# MCU.net
KiCad netlist of a schematic drawn in Altium Designer
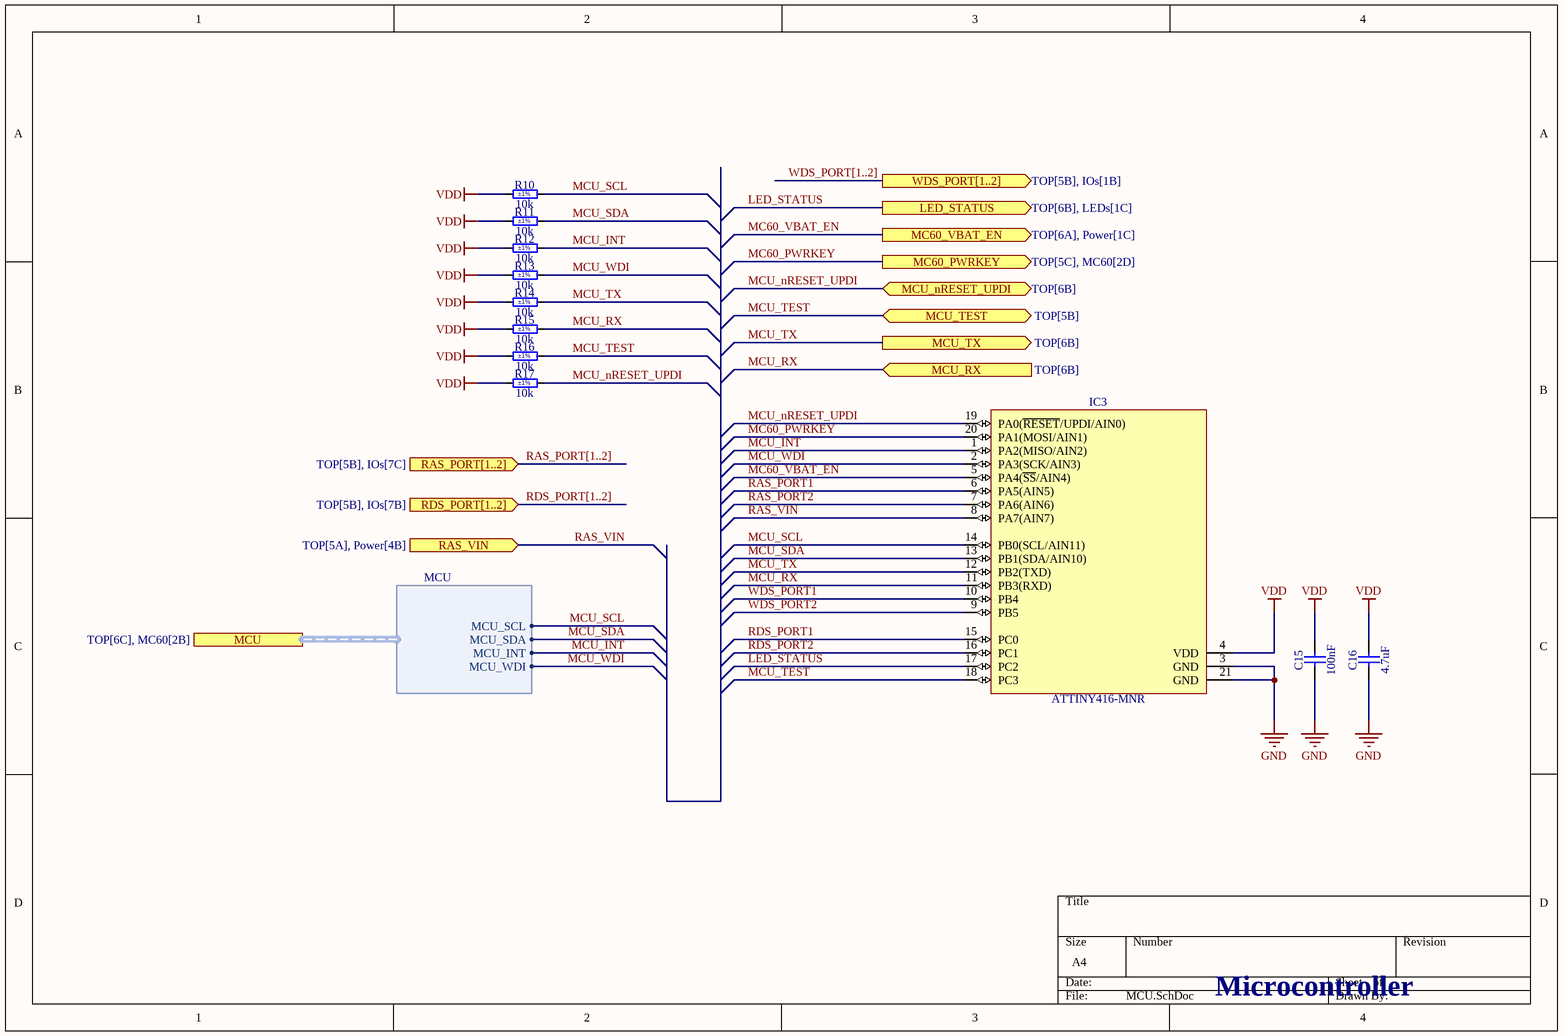
[diagram p0: MCU.SchDoc]

(export (version "E")
  (design (tool "Eeschema 10.0.6"))
  (components
    (comp (ref "C15")
      (value "100nF")
      (footprint "CAPC1608X87N")
      (description "Non-polarised capacitor")
      (fields
        (field (name "PART NUMBER") "CC0603_100NF_50V_10%_X7R")
        (field (name "VOLTAGE") "50V")
        (field (name "AUTHOR") "CERN DEM JLC")
      )
      (libsource (lib "Capacitors") (part "Capacitor - non polarized"))
    )
    (comp (ref "C16")
      (value "4.7uF")
      (footprint "CAPC1709X95N")
      (description "Non-polarised capacitor")
      (fields
        (field (name "PART NUMBER") "CC0603_4.7UF_16V_10%_X5R")
        (field (name "VOLTAGE") "16V")
        (field (name "AUTHOR") "CERN DEM JLC")
      )
      (libsource (lib "Capacitors") (part "Capacitor - non polarized"))
    )
    (comp (ref "IC3")
      (value "ATTINY416-MNR")
      (footprint "QFN40P300X300X80-21N-S180")
      (fields (field (name "MANUFACTURER") "MICROCHIP TECHNOLOGY") (field (name "AUTHOR") "Xusniyor"))
      (libsource (lib "ICs And Semiconductors") (part "ATTINY416-MNR"))
    )
    (comp (ref "R10")
      (value "10k")
      (footprint "RESC1608X55N")
      (description "Resistor - 1%")
      (fields
        (field (name "TOLERANCE") "±1%")
        (field (name "PART NUMBER") "R0603_10K_1%_0.1W_100PPM")
        (field (name "POWER") "0.1W")
        (field (name "AUTHOR") "CERN DEM JLC")
      )
      (libsource (lib "Resistors") (part "Resistor - 1%"))
    )
    (comp (ref "R11")
      (value "10k")
      (footprint "RESC1608X55N")
      (description "Resistor - 1%")
      (fields
        (field (name "TOLERANCE") "±1%")
        (field (name "PART NUMBER") "R0603_10K_1%_0.1W_100PPM")
        (field (name "POWER") "0.1W")
        (field (name "AUTHOR") "CERN DEM JLC")
      )
      (libsource (lib "Resistors") (part "Resistor - 1%"))
    )
    (comp (ref "R12")
      (value "10k")
      (footprint "RESC1608X55N")
      (description "Resistor - 1%")
      (fields
        (field (name "TOLERANCE") "±1%")
        (field (name "PART NUMBER") "R0603_10K_1%_0.1W_100PPM")
        (field (name "POWER") "0.1W")
        (field (name "AUTHOR") "CERN DEM JLC")
      )
      (libsource (lib "Resistors") (part "Resistor - 1%"))
    )
    (comp (ref "R13")
      (value "10k")
      (footprint "RESC1608X55N")
      (description "Resistor - 1%")
      (fields
        (field (name "TOLERANCE") "±1%")
        (field (name "PART NUMBER") "R0603_10K_1%_0.1W_100PPM")
        (field (name "POWER") "0.1W")
        (field (name "AUTHOR") "CERN DEM JLC")
      )
      (libsource (lib "Resistors") (part "Resistor - 1%"))
    )
    (comp (ref "R14")
      (value "10k")
      (footprint "RESC1608X55N")
      (description "Resistor - 1%")
      (fields
        (field (name "TOLERANCE") "±1%")
        (field (name "PART NUMBER") "R0603_10K_1%_0.1W_100PPM")
        (field (name "POWER") "0.1W")
        (field (name "AUTHOR") "CERN DEM JLC")
      )
      (libsource (lib "Resistors") (part "Resistor - 1%"))
    )
    (comp (ref "R15")
      (value "10k")
      (footprint "RESC1608X55N")
      (description "Resistor - 1%")
      (fields
        (field (name "TOLERANCE") "±1%")
        (field (name "PART NUMBER") "R0603_10K_1%_0.1W_100PPM")
        (field (name "POWER") "0.1W")
        (field (name "AUTHOR") "CERN DEM JLC")
      )
      (libsource (lib "Resistors") (part "Resistor - 1%"))
    )
    (comp (ref "R16")
      (value "10k")
      (footprint "RESC1608X55N")
      (description "Resistor - 1%")
      (fields
        (field (name "TOLERANCE") "±1%")
        (field (name "PART NUMBER") "R0603_10K_1%_0.1W_100PPM")
        (field (name "POWER") "0.1W")
        (field (name "AUTHOR") "CERN DEM JLC")
      )
      (libsource (lib "Resistors") (part "Resistor - 1%"))
    )
    (comp (ref "R17")
      (value "10k")
      (footprint "RESC1608X55N")
      (description "Resistor - 1%")
      (fields
        (field (name "TOLERANCE") "±1%")
        (field (name "PART NUMBER") "R0603_10K_1%_0.1W_100PPM")
        (field (name "POWER") "0.1W")
        (field (name "AUTHOR") "CERN DEM JLC")
      )
      (libsource (lib "Resistors") (part "Resistor - 1%"))
    )
  )
  (nets
    (net (code "2") (name "/LED_STATUS") (class "Default")
      (node (ref "IC3") (pin "17") (pinfunction "PC2_17") (pintype "bidirectional"))
    )
    (net (code "3") (name "/MC60_PWRKEY") (class "Default")
      (node (ref "IC3") (pin "20") (pinfunction "PA1(MOSI/AIN1)_20") (pintype "bidirectional"))
    )
    (net (code "4") (name "/MC60_VBAT_EN") (class "Default")
      (node (ref "IC3") (pin "5") (pinfunction "PA4(~{SS}/AIN4)_5") (pintype "bidirectional"))
    )
    (net (code "5") (name "/MCU_INT") (class "Default")
      (node (ref "IC3") (pin "1") (pinfunction "PA2(MISO/AIN2)_1") (pintype "bidirectional"))
      (node (ref "R12") (pin "2") (pinfunction "2_2") (pintype "passive"))
    )
    (net (code "6") (name "/MCU_RX") (class "Default")
      (node (ref "IC3") (pin "11") (pinfunction "PB3(RXD)_11") (pintype "bidirectional"))
      (node (ref "R15") (pin "2") (pinfunction "2_2") (pintype "passive"))
    )
    (net (code "7") (name "/MCU_SCL") (class "Default")
      (node (ref "IC3") (pin "14") (pinfunction "PB0(SCL/AIN11)_14") (pintype "bidirectional"))
      (node (ref "R10") (pin "2") (pinfunction "2_2") (pintype "passive"))
    )
    (net (code "8") (name "/MCU_SDA") (class "Default")
      (node (ref "IC3") (pin "13") (pinfunction "PB1(SDA/AIN10)_13") (pintype "bidirectional"))
      (node (ref "R11") (pin "2") (pinfunction "2_2") (pintype "passive"))
    )
    (net (code "9") (name "/MCU_TEST") (class "Default")
      (node (ref "IC3") (pin "18") (pinfunction "PC3_18") (pintype "bidirectional"))
      (node (ref "R16") (pin "2") (pinfunction "2_2") (pintype "passive"))
    )
    (net (code "10") (name "/MCU_TX") (class "Default")
      (node (ref "IC3") (pin "12") (pinfunction "PB2(TXD)_12") (pintype "bidirectional"))
      (node (ref "R14") (pin "2") (pinfunction "2_2") (pintype "passive"))
    )
    (net (code "11") (name "/MCU_WDI") (class "Default")
      (node (ref "IC3") (pin "2") (pinfunction "PA3(SCK/AIN3)_2") (pintype "bidirectional"))
      (node (ref "R13") (pin "2") (pinfunction "2_2") (pintype "passive"))
    )
    (net (code "12") (name "/MCU_nRESET_UPDI") (class "Default")
      (node (ref "IC3") (pin "19") (pinfunction "PA0(~{RESET}/UPDI/AIN0)_19") (pintype "bidirectional"))
      (node (ref "R17") (pin "2") (pinfunction "2_2") (pintype "passive"))
    )
    (net (code "13") (name "/RAS_PORT1") (class "Default")
      (node (ref "IC3") (pin "6") (pinfunction "PA5(AIN5)_6") (pintype "bidirectional"))
    )
    (net (code "14") (name "/RAS_PORT2") (class "Default")
      (node (ref "IC3") (pin "7") (pinfunction "PA6(AIN6)_7") (pintype "bidirectional"))
    )
    (net (code "16") (name "/RAS_VIN") (class "Default")
      (node (ref "IC3") (pin "8") (pinfunction "PA7(AIN7)_8") (pintype "bidirectional"))
    )
    (net (code "17") (name "/RDS_PORT1") (class "Default")
      (node (ref "IC3") (pin "15") (pinfunction "PC0_15") (pintype "bidirectional"))
    )
    (net (code "18") (name "/RDS_PORT2") (class "Default")
      (node (ref "IC3") (pin "16") (pinfunction "PC1_16") (pintype "bidirectional"))
    )
    (net (code "20") (name "/WDS_PORT1") (class "Default")
      (node (ref "IC3") (pin "10") (pinfunction "PB4_10") (pintype "bidirectional"))
    )
    (net (code "21") (name "/WDS_PORT2") (class "Default")
      (node (ref "IC3") (pin "9") (pinfunction "PB5_9") (pintype "bidirectional"))
    )
    (net (code "24") (name "GND") (class "Default")
      (node (ref "C15") (pin "1") (pinfunction "1_1") (pintype "passive"))
      (node (ref "C16") (pin "1") (pinfunction "1_1") (pintype "passive"))
      (node (ref "IC3") (pin "21") (pinfunction "GND_21") (pintype "passive"))
      (node (ref "IC3") (pin "3") (pinfunction "GND_3") (pintype "passive"))
    )
    (net (code "25") (name "VDD") (class "Default")
      (node (ref "C15") (pin "2") (pinfunction "2_2") (pintype "passive"))
      (node (ref "C16") (pin "2") (pinfunction "2_2") (pintype "passive"))
      (node (ref "IC3") (pin "4") (pinfunction "VDD_4") (pintype "passive"))
      (node (ref "R10") (pin "1") (pinfunction "1_1") (pintype "passive"))
      (node (ref "R11") (pin "1") (pinfunction "1_1") (pintype "passive"))
      (node (ref "R12") (pin "1") (pinfunction "1_1") (pintype "passive"))
      (node (ref "R13") (pin "1") (pinfunction "1_1") (pintype "passive"))
      (node (ref "R14") (pin "1") (pinfunction "1_1") (pintype "passive"))
      (node (ref "R15") (pin "1") (pinfunction "1_1") (pintype "passive"))
      (node (ref "R16") (pin "1") (pinfunction "1_1") (pintype "passive"))
      (node (ref "R17") (pin "1") (pinfunction "1_1") (pintype "passive"))
    )
  )
)
